# P1_Alim.net
KiCad netlist of a schematic drawn in Altium Designer
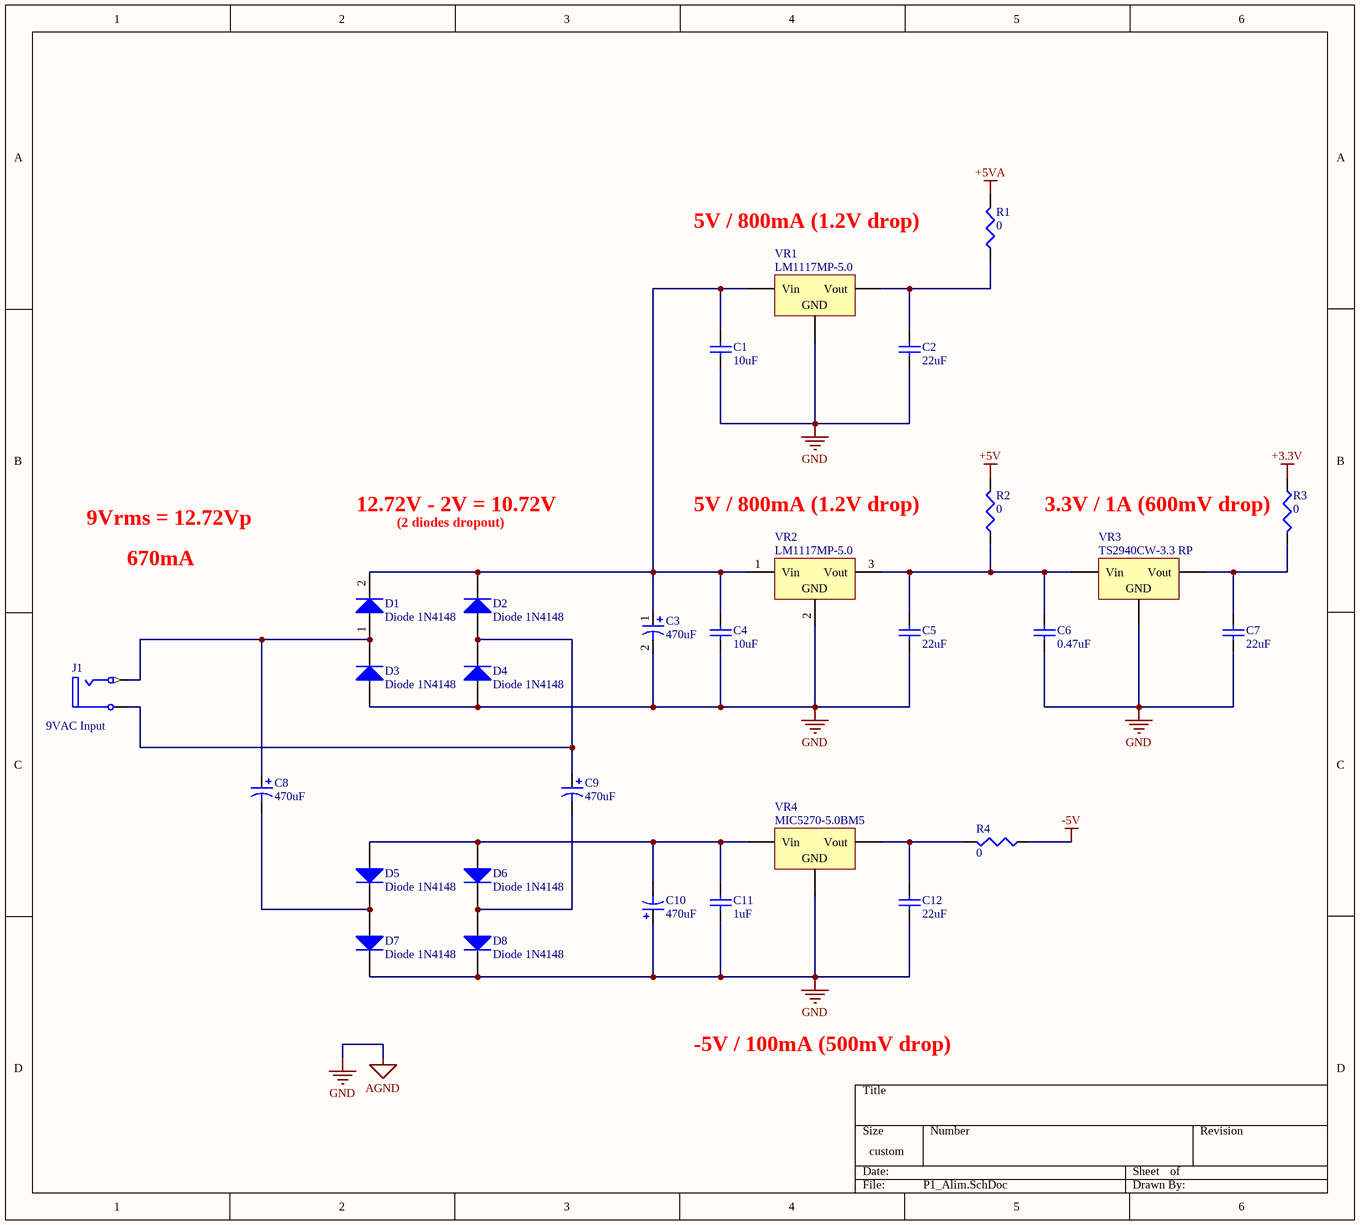
[diagram p0: P1_Alim.SchDoc]

(export (version "E")
  (design (tool "Eeschema 10.0.6"))
  (components
    (comp (ref "C1")
      (value "10uF")
      (footprint "CAP 0603 (1608 metric)")
      (description "Capacitor (Semiconductor SIM Model)")
      (libsource (lib "Miscellaneous Devices") (part "Cap Semi"))
    )
    (comp (ref "C2")
      (value "22uF")
      (footprint "CAP 0603 (1608 metric)")
      (description "Capacitor (Semiconductor SIM Model)")
      (libsource (lib "Miscellaneous Devices") (part "Cap Semi"))
    )
    (comp (ref "C3")
      (value "470uF")
      (footprint "Condo Electro 5mm")
      (description "Polarized Capacitor (Radial)")
      (libsource (lib "") (part "Cap Pol1_1"))
    )
    (comp (ref "C4")
      (value "10uF")
      (footprint "CAP 0603 (1608 metric)")
      (description "Capacitor (Semiconductor SIM Model)")
      (libsource (lib "Miscellaneous Devices") (part "Cap Semi"))
    )
    (comp (ref "C5")
      (value "22uF")
      (footprint "CAP 0603 (1608 metric)")
      (description "Capacitor (Semiconductor SIM Model)")
      (libsource (lib "Miscellaneous Devices") (part "Cap Semi"))
    )
    (comp (ref "C6")
      (value "0.47uF")
      (footprint "CAP 0603 (1608 metric)")
      (description "Capacitor (Semiconductor SIM Model)")
      (libsource (lib "Miscellaneous Devices") (part "Cap Semi"))
    )
    (comp (ref "C7")
      (value "22uF")
      (footprint "CAP 0603 (1608 metric)")
      (description "Capacitor (Semiconductor SIM Model)")
      (libsource (lib "Miscellaneous Devices") (part "Cap Semi"))
    )
    (comp (ref "C8")
      (value "470uF")
      (footprint "Condo Electro 5mm")
      (description "Polarized Capacitor (Radial)")
      (libsource (lib "Miscellaneous Devices") (part "Cap Pol1"))
    )
    (comp (ref "C9")
      (value "470uF")
      (footprint "Condo Electro 5mm")
      (description "Polarized Capacitor (Radial)")
      (libsource (lib "Miscellaneous Devices") (part "Cap Pol1"))
    )
    (comp (ref "C10")
      (value "470uF")
      (footprint "Condo Electro 5mm")
      (description "Polarized Capacitor (Radial)")
      (libsource (lib "Miscellaneous Devices") (part "Cap Pol1"))
    )
    (comp (ref "C11")
      (value "1uF")
      (footprint "CAP 0603 (1608 metric)")
      (description "Capacitor (Semiconductor SIM Model)")
      (libsource (lib "Miscellaneous Devices") (part "Cap Semi"))
    )
    (comp (ref "C12")
      (value "22uF")
      (footprint "CAP 0603 (1608 metric)")
      (description "Capacitor (Semiconductor SIM Model)")
      (libsource (lib "Miscellaneous Devices") (part "Cap Semi"))
    )
    (comp (ref "D1")
      (value "Diode 1N4148")
      (footprint "1N4148")
      (description "High Conductance Fast Diode")
      (libsource (lib "") (part "Diode 1N4148_1"))
    )
    (comp (ref "D2")
      (value "Diode 1N4148")
      (footprint "1N4148")
      (description "High Conductance Fast Diode")
      (libsource (lib "Miscellaneous Devices") (part "Diode 1N4148"))
    )
    (comp (ref "D3")
      (value "Diode 1N4148")
      (footprint "1N4148")
      (description "High Conductance Fast Diode")
      (libsource (lib "Miscellaneous Devices") (part "Diode 1N4148"))
    )
    (comp (ref "D4")
      (value "Diode 1N4148")
      (footprint "1N4148")
      (description "High Conductance Fast Diode")
      (libsource (lib "Miscellaneous Devices") (part "Diode 1N4148"))
    )
    (comp (ref "D5")
      (value "Diode 1N4148")
      (footprint "1N4148")
      (description "High Conductance Fast Diode")
      (libsource (lib "Miscellaneous Devices") (part "Diode 1N4148"))
    )
    (comp (ref "D6")
      (value "Diode 1N4148")
      (footprint "1N4148")
      (description "High Conductance Fast Diode")
      (libsource (lib "Miscellaneous Devices") (part "Diode 1N4148"))
    )
    (comp (ref "D7")
      (value "Diode 1N4148")
      (footprint "1N4148")
      (description "High Conductance Fast Diode")
      (libsource (lib "Miscellaneous Devices") (part "Diode 1N4148"))
    )
    (comp (ref "D8")
      (value "Diode 1N4148")
      (footprint "1N4148")
      (description "High Conductance Fast Diode")
      (libsource (lib "Miscellaneous Devices") (part "Diode 1N4148"))
    )
    (comp (ref "J1")
      (value "9VAC Input")
      (description "Jack Socket, 1/4\" [6.5mm], Thru-Hole, Vertical, 2-Conductor Open Circuit")
      (libsource (lib "Miscellaneous Connectors") (part "Phonejack2"))
    )
    (comp (ref "R1")
      (value "0")
      (footprint "RES 0603 (1608 metric)")
      (description "Resistor")
      (libsource (lib "Miscellaneous Devices") (part "Res3"))
    )
    (comp (ref "R2")
      (value "0")
      (footprint "RES 0603 (1608 metric)")
      (description "Resistor")
      (libsource (lib "Miscellaneous Devices") (part "Res3"))
    )
    (comp (ref "R3")
      (value "0")
      (footprint "RES 0603 (1608 metric)")
      (description "Resistor")
      (libsource (lib "Miscellaneous Devices") (part "Res3"))
    )
    (comp (ref "R4")
      (value "0")
      (footprint "RES 0603 (1608 metric)")
      (description "Resistor")
      (libsource (lib "Miscellaneous Devices") (part "Res3"))
    )
    (comp (ref "VR1")
      (value "LM1117MP-5.0")
      (footprint "SOT-223")
      (description "Voltage Regulator")
      (libsource (lib "Miscellaneous Devices") (part "Volt Reg"))
    )
    (comp (ref "VR2")
      (value "LM1117MP-5.0")
      (footprint "SOT-223")
      (description "Voltage Regulator")
      (libsource (lib "") (part "Volt Reg_1"))
    )
    (comp (ref "VR3")
      (value "TS2940CW-3.3 RP")
      (footprint "SOT-223")
      (description "Voltage Regulator")
      (libsource (lib "Miscellaneous Devices") (part "Volt Reg"))
    )
    (comp (ref "VR4")
      (value "MIC5270-5.0BM5")
      (description "Voltage Regulator")
      (libsource (lib "Miscellaneous Devices") (part "Volt Reg"))
    )
  )
  (nets
    (net (code "1") (name "+3.3V") (class "Default")
      (node (ref "R3") (pin "1") (pinfunction "1_1") (pintype "passive"))
    )
    (net (code "2") (name "+5V") (class "Default")
      (node (ref "R2") (pin "2") (pinfunction "2_2") (pintype "passive"))
    )
    (net (code "3") (name "+5VA") (class "Default")
      (node (ref "R1") (pin "2") (pinfunction "2_2") (pintype "passive"))
    )
    (net (code "4") (name "-5V") (class "Default")
      (node (ref "R4") (pin "1") (pinfunction "1_1") (pintype "passive"))
    )
    (net (code "5") (name "AGND") (class "Default")
      (node (ref "C1") (pin "1") (pinfunction "1_1") (pintype "passive"))
      (node (ref "C10") (pin "1") (pinfunction "1_1") (pintype "passive"))
      (node (ref "C11") (pin "1") (pinfunction "1_1") (pintype "passive"))
      (node (ref "C12") (pin "1") (pinfunction "1_1") (pintype "passive"))
      (node (ref "C2") (pin "1") (pinfunction "1_1") (pintype "passive"))
      (node (ref "C3") (pin "2") (pinfunction "2_2") (pintype "passive"))
      (node (ref "C4") (pin "1") (pinfunction "1_1") (pintype "passive"))
      (node (ref "C5") (pin "1") (pinfunction "1_1") (pintype "passive"))
      (node (ref "C6") (pin "1") (pinfunction "1_1") (pintype "passive"))
      (node (ref "C7") (pin "1") (pinfunction "1_1") (pintype "passive"))
      (node (ref "D3") (pin "1") (pinfunction "A_1") (pintype "passive"))
      (node (ref "D4") (pin "1") (pinfunction "A_1") (pintype "passive"))
      (node (ref "D7") (pin "2") (pinfunction "K_2") (pintype "passive"))
      (node (ref "D8") (pin "2") (pinfunction "K_2") (pintype "passive"))
      (node (ref "VR1") (pin "2") (pinfunction "GND_2") (pintype "passive"))
      (node (ref "VR2") (pin "2") (pinfunction "GND_2") (pintype "passive"))
      (node (ref "VR3") (pin "2") (pinfunction "GND_2") (pintype "passive"))
      (node (ref "VR4") (pin "2") (pinfunction "GND_2") (pintype "passive"))
    )
    (net (code "6") (name "Net-(D1-A)") (class "Default")
      (node (ref "C8") (pin "1") (pinfunction "1_1") (pintype "passive"))
      (node (ref "D1") (pin "1") (pinfunction "A_1") (pintype "passive"))
      (node (ref "D3") (pin "2") (pinfunction "K_2") (pintype "passive"))
      (node (ref "J1") (pin "1") (pinfunction "T_1") (pintype "output"))
    )
    (net (code "7") (name "Net-(D1-K)") (class "Default")
      (node (ref "C1") (pin "2") (pinfunction "2_2") (pintype "passive"))
      (node (ref "C3") (pin "1") (pinfunction "1_1") (pintype "passive"))
      (node (ref "C4") (pin "2") (pinfunction "2_2") (pintype "passive"))
      (node (ref "D1") (pin "2") (pinfunction "K_2") (pintype "passive"))
      (node (ref "D2") (pin "2") (pinfunction "K_2") (pintype "passive"))
      (node (ref "VR1") (pin "1") (pinfunction "Vin_1") (pintype "passive"))
      (node (ref "VR2") (pin "1") (pinfunction "Vin_1") (pintype "passive"))
    )
    (net (code "8") (name "Net-(D2-A)") (class "Default")
      (node (ref "C9") (pin "1") (pinfunction "1_1") (pintype "passive"))
      (node (ref "D2") (pin "1") (pinfunction "A_1") (pintype "passive"))
      (node (ref "D4") (pin "2") (pinfunction "K_2") (pintype "passive"))
      (node (ref "J1") (pin "5") (pinfunction "S_5") (pintype "power_in"))
    )
    (net (code "9") (name "Net-(D5-A)") (class "Default")
      (node (ref "C10") (pin "2") (pinfunction "2_2") (pintype "passive"))
      (node (ref "C11") (pin "2") (pinfunction "2_2") (pintype "passive"))
      (node (ref "D5") (pin "1") (pinfunction "A_1") (pintype "passive"))
      (node (ref "D6") (pin "1") (pinfunction "A_1") (pintype "passive"))
      (node (ref "VR4") (pin "1") (pinfunction "Vin_1") (pintype "passive"))
    )
    (net (code "10") (name "Net-(D5-K)") (class "Default")
      (node (ref "C8") (pin "2") (pinfunction "2_2") (pintype "passive"))
      (node (ref "D5") (pin "2") (pinfunction "K_2") (pintype "passive"))
      (node (ref "D7") (pin "1") (pinfunction "A_1") (pintype "passive"))
    )
    (net (code "11") (name "Net-(D6-K)") (class "Default")
      (node (ref "C9") (pin "2") (pinfunction "2_2") (pintype "passive"))
      (node (ref "D6") (pin "2") (pinfunction "K_2") (pintype "passive"))
      (node (ref "D8") (pin "1") (pinfunction "A_1") (pintype "passive"))
    )
    (net (code "12") (name "Net-(VR1-Vout)") (class "Default")
      (node (ref "C2") (pin "2") (pinfunction "2_2") (pintype "passive"))
      (node (ref "R1") (pin "1") (pinfunction "1_1") (pintype "passive"))
      (node (ref "VR1") (pin "3") (pinfunction "Vout_3") (pintype "passive"))
    )
    (net (code "13") (name "Net-(VR2-Vout)") (class "Default")
      (node (ref "C5") (pin "2") (pinfunction "2_2") (pintype "passive"))
      (node (ref "C6") (pin "2") (pinfunction "2_2") (pintype "passive"))
      (node (ref "R2") (pin "1") (pinfunction "1_1") (pintype "passive"))
      (node (ref "VR2") (pin "3") (pinfunction "Vout_3") (pintype "passive"))
      (node (ref "VR3") (pin "1") (pinfunction "Vin_1") (pintype "passive"))
    )
    (net (code "14") (name "Net-(VR3-Vout)") (class "Default")
      (node (ref "C7") (pin "2") (pinfunction "2_2") (pintype "passive"))
      (node (ref "R3") (pin "2") (pinfunction "2_2") (pintype "passive"))
      (node (ref "VR3") (pin "3") (pinfunction "Vout_3") (pintype "passive"))
    )
    (net (code "15") (name "Net-(VR4-Vout)") (class "Default")
      (node (ref "C12") (pin "2") (pinfunction "2_2") (pintype "passive"))
      (node (ref "R4") (pin "2") (pinfunction "2_2") (pintype "passive"))
      (node (ref "VR4") (pin "3") (pinfunction "Vout_3") (pintype "passive"))
    )
  )
)
